# STRWL-S06-V00-Peripherals.net
KiCad netlist of a schematic drawn in Altium Designer
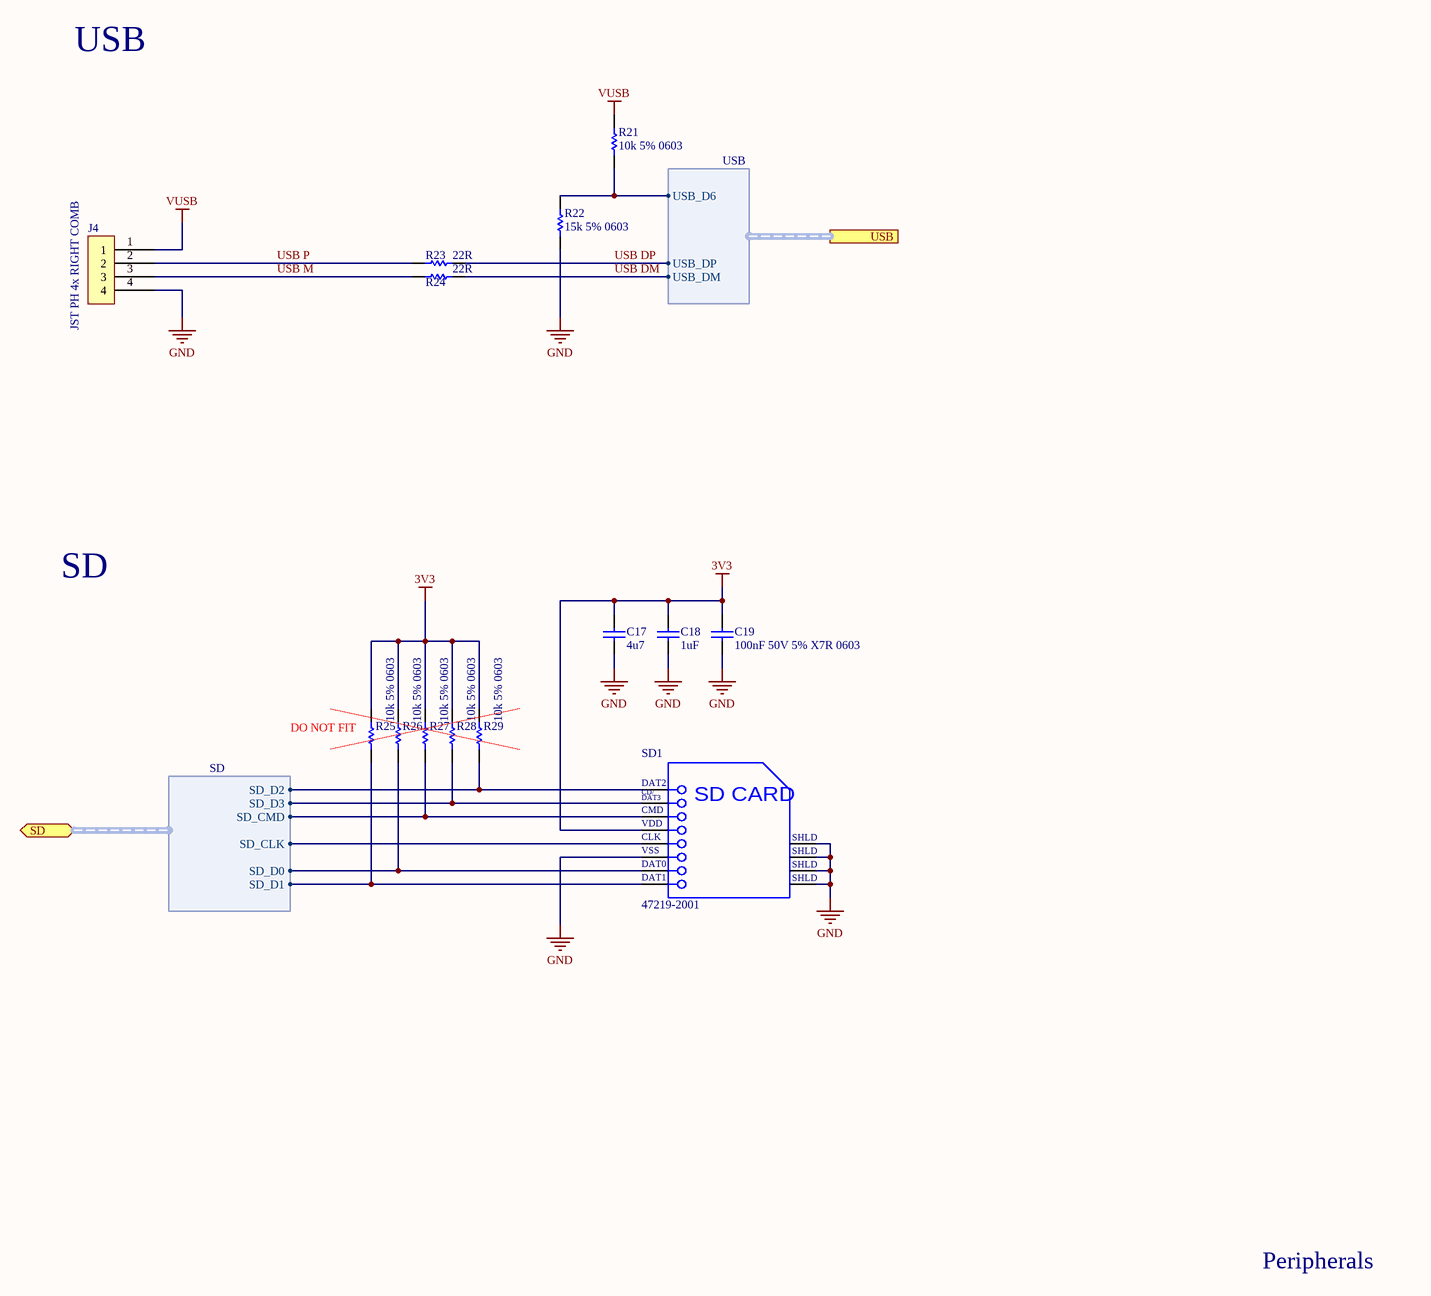
[diagram p0: STRWL-S06-V00-Peripherals.SchDoc]

(export (version "E")
  (design (tool "Eeschema 10.0.6"))
  (components
    (comp (ref "C17")
      (value "4u7")
      (footprint "Cap_Ceramic_0603")
      (description "Capacitor, Ceramic, SMD, 4u7, 50V, 5%, X7R, 0603")
      (libsource (lib "StandardCapacitors") (part "4u7 50V 5% X7R 0603"))
    )
    (comp (ref "C18")
      (value "1uF")
      (footprint "Cap_Ceramic_0603")
      (description "Capacitor, Ceramic, SMD, 1uF, 25V, 5%, X7R, 0603")
      (libsource (lib "StandardCapacitors") (part "1uF 25V 5% X7R 0603"))
    )
    (comp (ref "C19")
      (value "100nF 50V 5% X7R 0603")
      (footprint "Cap_Ceramic_0603")
      (description "Capacitor, Ceramic, SMD, 100nF, 50V, 5%, X7R, 0603")
      (libsource (lib "StandardCapacitors") (part "100nF 50V 5% X7R 0603"))
    )
    (comp (ref "J4")
      (value "JST PH 4x RIGHT COMB")
      (footprint "JST PH 4x RIGHT COMB")
      (libsource (lib "QUTMS-MCISOLibrary") (part "JST PH 4x RIGHT COMB"))
    )
    (comp (ref "R21")
      (value "10k 5% 0603")
      (footprint "Res_ThinFilm_0603")
      (description "Resistor, SMD, 10k, 0.1W, 5%, 0603")
      (libsource (lib "StandardResistors") (part "10k 5% 0603"))
    )
    (comp (ref "R22")
      (value "15k 5% 0603")
      (footprint "Res_ThinFilm_0603")
      (description "Resistor, SMD, 15k, 0.1W, 5%, 0603")
      (libsource (lib "StandardResistors") (part "15k 5% 0603"))
    )
    (comp (ref "R23")
      (value "22R")
      (footprint "Res_ThinFilm_0603")
      (description "Resistor, SMD, 22R, 0.1W, 1%, 0603")
      (libsource (lib "QUTMS-MCISOLibrary") (part "22R 1% 0603"))
    )
    (comp (ref "R24")
      (value "22R")
      (footprint "Res_ThinFilm_0603")
      (description "Resistor, SMD, 22R, 0.1W, 1%, 0603")
      (libsource (lib "QUTMS-MCISOLibrary") (part "22R 1% 0603"))
    )
    (comp (ref "R25")
      (value "10k 5% 0603")
      (footprint "Res_ThinFilm_0603")
      (description "Resistor, SMD, 10k, 0.1W, 5%, 0603")
      (libsource (lib "StandardResistors") (part "10k 5% 0603"))
    )
    (comp (ref "R26")
      (value "10k 5% 0603")
      (footprint "Res_ThinFilm_0603")
      (description "Resistor, SMD, 10k, 0.1W, 5%, 0603")
      (libsource (lib "StandardResistors") (part "10k 5% 0603"))
    )
    (comp (ref "R27")
      (value "10k 5% 0603")
      (footprint "Res_ThinFilm_0603")
      (description "Resistor, SMD, 10k, 0.1W, 5%, 0603")
      (libsource (lib "StandardResistors") (part "10k 5% 0603"))
    )
    (comp (ref "R28")
      (value "10k 5% 0603")
      (footprint "Res_ThinFilm_0603")
      (description "Resistor, SMD, 10k, 0.1W, 5%, 0603")
      (libsource (lib "StandardResistors") (part "10k 5% 0603"))
    )
    (comp (ref "R29")
      (value "10k 5% 0603")
      (footprint "Res_ThinFilm_0603")
      (description "Resistor, SMD, 10k, 0.1W, 5%, 0603")
      (libsource (lib "StandardResistors") (part "10k 5% 0603"))
    )
    (comp (ref "SD1")
      (value "47219-2001")
      (footprint "47219-2001")
      (description "MicroSD Card Connector, Hinge Type, -40 to 85 degC, 8-Pin SMD, RoHS, Tape and Reel")
      (libsource (lib "QUTMS-MCISOLibrary") (part "47219-2001"))
    )
  )
  (nets
    (net (code "3") (name "/SD_CLK") (class "Default")
      (node (ref "SD1") (pin "5") (pinfunction "CLK_5") (pintype "passive"))
    )
    (net (code "4") (name "/SD_CMD") (class "Default")
      (node (ref "R27") (pin "1") (pinfunction "1_1") (pintype "passive"))
      (node (ref "SD1") (pin "3") (pinfunction "CMD_3") (pintype "passive"))
    )
    (net (code "5") (name "/SD_D0") (class "Default")
      (node (ref "R26") (pin "1") (pinfunction "1_1") (pintype "passive"))
      (node (ref "SD1") (pin "7") (pinfunction "DAT0_7") (pintype "passive"))
    )
    (net (code "6") (name "/SD_D1") (class "Default")
      (node (ref "R25") (pin "1") (pinfunction "1_1") (pintype "passive"))
      (node (ref "SD1") (pin "8") (pinfunction "DAT1_8") (pintype "passive"))
    )
    (net (code "7") (name "/SD_D2") (class "Default")
      (node (ref "R29") (pin "1") (pinfunction "1_1") (pintype "passive"))
      (node (ref "SD1") (pin "1") (pinfunction "DAT2_1") (pintype "passive"))
    )
    (net (code "8") (name "/SD_D3") (class "Default")
      (node (ref "R28") (pin "1") (pinfunction "1_1") (pintype "passive"))
      (node (ref "SD1") (pin "2") (pinfunction "CD/DAT3_2") (pintype "passive"))
    )
    (net (code "9") (name "/USB DM") (class "Default")
      (node (ref "R24") (pin "2") (pinfunction "2_2") (pintype "passive"))
    )
    (net (code "10") (name "/USB DP") (class "Default")
      (node (ref "R23") (pin "2") (pinfunction "2_2") (pintype "passive"))
    )
    (net (code "11") (name "/USB M") (class "Default")
      (node (ref "J4") (pin "3") (pinfunction "3_3") (pintype "passive"))
      (node (ref "R24") (pin "1") (pinfunction "1_1") (pintype "passive"))
    )
    (net (code "12") (name "/USB P") (class "Default")
      (node (ref "J4") (pin "2") (pinfunction "2_2") (pintype "passive"))
      (node (ref "R23") (pin "1") (pinfunction "1_1") (pintype "passive"))
    )
    (net (code "13") (name "/USB_D6") (class "Default")
      (node (ref "R21") (pin "1") (pinfunction "1_1") (pintype "passive"))
      (node (ref "R22") (pin "2") (pinfunction "2_2") (pintype "passive"))
    )
    (net (code "16") (name "3V3") (class "Default")
      (node (ref "C17") (pin "2") (pinfunction "2_2") (pintype "passive"))
      (node (ref "C18") (pin "2") (pinfunction "2_2") (pintype "passive"))
      (node (ref "C19") (pin "2") (pinfunction "2_2") (pintype "passive"))
      (node (ref "R25") (pin "2") (pinfunction "2_2") (pintype "passive"))
      (node (ref "R26") (pin "2") (pinfunction "2_2") (pintype "passive"))
      (node (ref "R27") (pin "2") (pinfunction "2_2") (pintype "passive"))
      (node (ref "R28") (pin "2") (pinfunction "2_2") (pintype "passive"))
      (node (ref "R29") (pin "2") (pinfunction "2_2") (pintype "passive"))
      (node (ref "SD1") (pin "4") (pinfunction "VDD_4") (pintype "passive"))
    )
    (net (code "17") (name "GND") (class "Default")
      (node (ref "C17") (pin "1") (pinfunction "1_1") (pintype "passive"))
      (node (ref "C18") (pin "1") (pinfunction "1_1") (pintype "passive"))
      (node (ref "C19") (pin "1") (pinfunction "1_1") (pintype "passive"))
      (node (ref "J4") (pin "4") (pinfunction "4_4") (pintype "passive"))
      (node (ref "R22") (pin "1") (pinfunction "1_1") (pintype "passive"))
      (node (ref "SD1") (pin "10") (pinfunction "SHLD_10") (pintype "passive"))
      (node (ref "SD1") (pin "11") (pinfunction "SHLD_11") (pintype "passive"))
      (node (ref "SD1") (pin "12") (pinfunction "SHLD_12") (pintype "passive"))
      (node (ref "SD1") (pin "6") (pinfunction "VSS_6") (pintype "passive"))
      (node (ref "SD1") (pin "9") (pinfunction "SHLD_9") (pintype "passive"))
    )
    (net (code "18") (name "VUSB") (class "Default")
      (node (ref "J4") (pin "1") (pinfunction "1_1") (pintype "passive"))
      (node (ref "R21") (pin "2") (pinfunction "2_2") (pintype "passive"))
    )
  )
)
